# cryobondr-qbit2-pqc.net
KiCad netlist of a schematic drawn in EAGLE
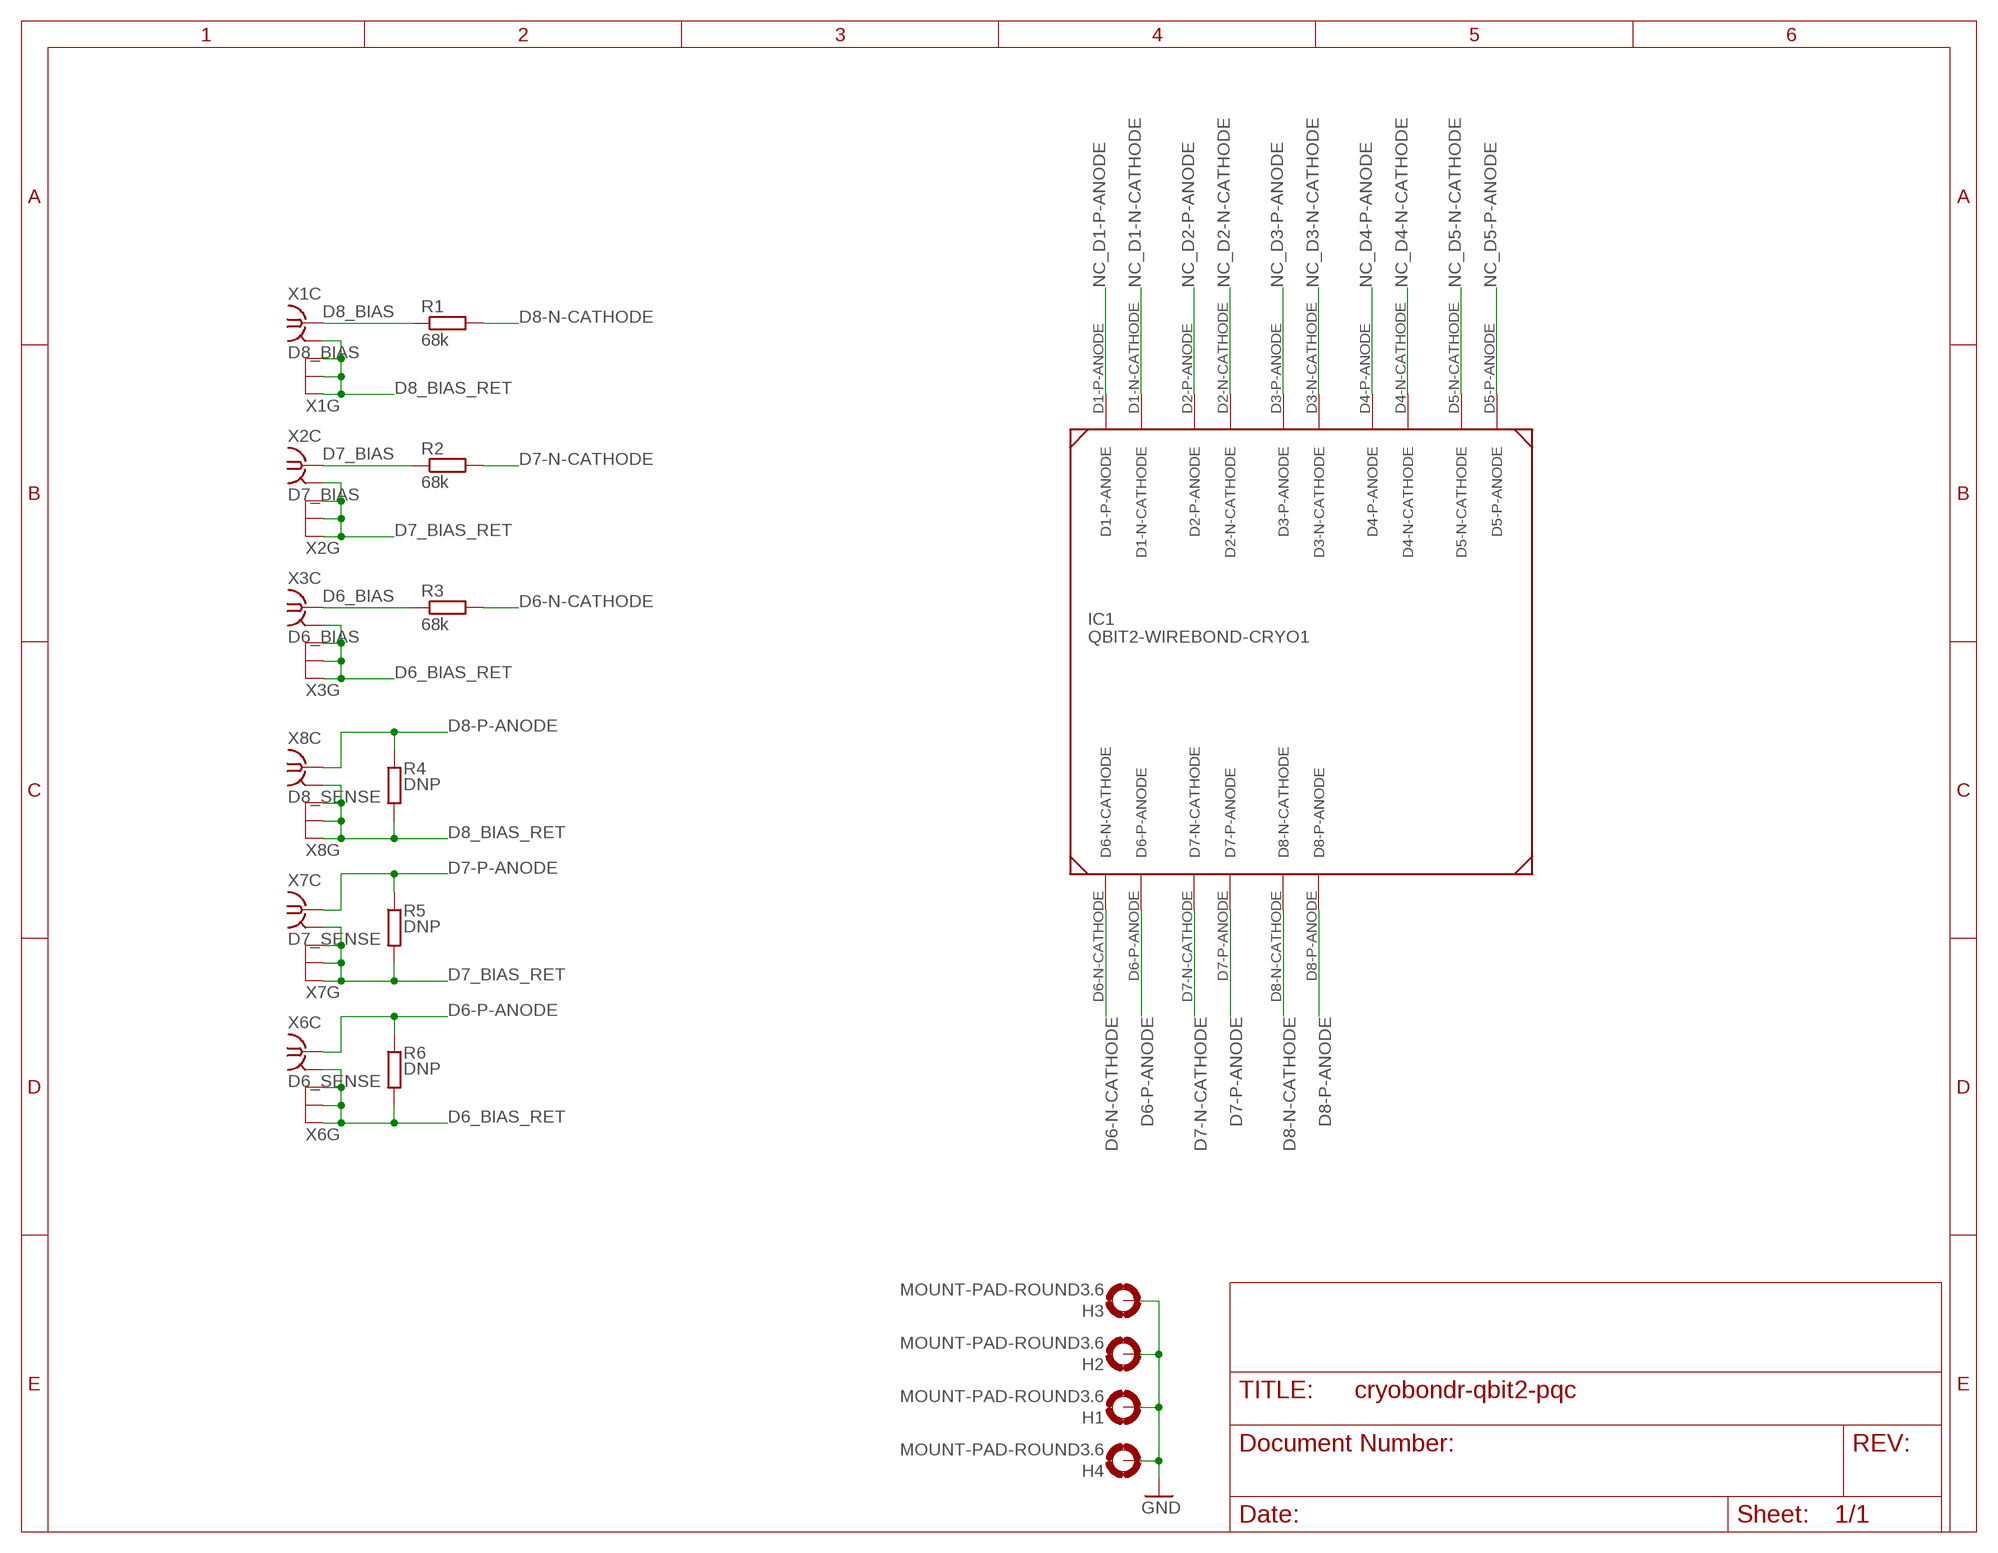
[diagram p0: schematic, sheet 1]

(export (version "E")
  (design (tool "Eeschema 10.0.6"))
  (components
    (comp (ref "H1")
      (value "MOUNT-PAD-ROUND3.6")
      (footprint "eagle-import:3,6-PAD")
      (libsource (lib "eagle-import") (part "MOUNT-PAD-ROUND3.6"))
    )
    (comp (ref "H2")
      (value "MOUNT-PAD-ROUND3.6")
      (footprint "eagle-import:3,6-PAD")
      (libsource (lib "eagle-import") (part "MOUNT-PAD-ROUND3.6"))
    )
    (comp (ref "H3")
      (value "MOUNT-PAD-ROUND3.6")
      (footprint "eagle-import:3,6-PAD")
      (libsource (lib "eagle-import") (part "MOUNT-PAD-ROUND3.6"))
    )
    (comp (ref "H4")
      (value "MOUNT-PAD-ROUND3.6")
      (footprint "eagle-import:3,6-PAD")
      (libsource (lib "eagle-import") (part "MOUNT-PAD-ROUND3.6"))
    )
    (comp (ref "IC1")
      (value "QBIT2-WIREBOND-CRYO1")
      (footprint "eagle-import:QBIT2-WIREBOND-CRYO1")
      (libsource (lib "eagle-import") (part "QBIT2-WIREBOND-CRYO1"))
    )
    (comp (ref "R1")
      (value "68k")
      (footprint "eagle-import:R0603")
      (libsource (lib "eagle-import") (part "R-EU_R0603"))
    )
    (comp (ref "R2")
      (value "68k")
      (footprint "eagle-import:R0603")
      (libsource (lib "eagle-import") (part "R-EU_R0603"))
    )
    (comp (ref "R3")
      (value "68k")
      (footprint "eagle-import:R0603")
      (libsource (lib "eagle-import") (part "R-EU_R0603"))
    )
    (comp (ref "R4")
      (value "DNP")
      (footprint "eagle-import:R0603")
      (libsource (lib "eagle-import") (part "R-EU_R0603"))
    )
    (comp (ref "R5")
      (value "DNP")
      (footprint "eagle-import:R0603")
      (libsource (lib "eagle-import") (part "R-EU_R0603"))
    )
    (comp (ref "R6")
      (value "DNP")
      (footprint "eagle-import:R0603")
      (libsource (lib "eagle-import") (part "R-EU_R0603"))
    )
    (comp (ref "X1")
      (value "D8_BIAS")
      (footprint "eagle-import:MMCX-SMT")
      (libsource (lib "eagle-import") (part "MMCX"))
    )
    (comp (ref "X2")
      (value "D7_BIAS")
      (footprint "eagle-import:MMCX-SMT")
      (libsource (lib "eagle-import") (part "MMCX"))
    )
    (comp (ref "X3")
      (value "D6_BIAS")
      (footprint "eagle-import:MMCX-SMT")
      (libsource (lib "eagle-import") (part "MMCX"))
    )
    (comp (ref "X6")
      (value "D6_SENSE")
      (footprint "eagle-import:MMCX-SMT")
      (libsource (lib "eagle-import") (part "MMCX"))
    )
    (comp (ref "X7")
      (value "D7_SENSE")
      (footprint "eagle-import:MMCX-SMT")
      (libsource (lib "eagle-import") (part "MMCX"))
    )
    (comp (ref "X8")
      (value "D8_SENSE")
      (footprint "eagle-import:MMCX-SMT")
      (libsource (lib "eagle-import") (part "MMCX"))
    )
  )
  (nets
    (net (code "1") (name "/D6-N-CATHODE") (class "Default")
      (node (ref "IC1") (pin "D6-N-CATHODE") (pinfunction "D6-N-CATHODE_D6-N-CATHODE") (pintype "bidirectional"))
      (node (ref "R3") (pin "2") (pinfunction "2_2") (pintype "passive"))
    )
    (net (code "2") (name "/D6-P-ANODE") (class "Default")
      (node (ref "IC1") (pin "D6-P-ANODE") (pinfunction "D6-P-ANODE_D6-P-ANODE") (pintype "bidirectional"))
      (node (ref "R6") (pin "1") (pinfunction "1_1") (pintype "passive"))
      (node (ref "X6") (pin "S") (pinfunction "1_S") (pintype "passive"))
    )
    (net (code "3") (name "/D6_BIAS") (class "Default")
      (node (ref "R3") (pin "1") (pinfunction "1_1") (pintype "passive"))
      (node (ref "X3") (pin "S") (pinfunction "1_S") (pintype "passive"))
    )
    (net (code "4") (name "/D6_BIAS_RET") (class "Default")
      (node (ref "R6") (pin "2") (pinfunction "2_2") (pintype "passive"))
      (node (ref "X3") (pin "G1") (pinfunction "GND_G1") (pintype "power_in"))
      (node (ref "X3") (pin "G2") (pinfunction "GND_G2") (pintype "power_in"))
      (node (ref "X3") (pin "G3") (pinfunction "GND_G3") (pintype "power_in"))
      (node (ref "X3") (pin "G4") (pinfunction "GND_G4") (pintype "power_in"))
      (node (ref "X6") (pin "G1") (pinfunction "GND_G1") (pintype "power_in"))
      (node (ref "X6") (pin "G2") (pinfunction "GND_G2") (pintype "power_in"))
      (node (ref "X6") (pin "G3") (pinfunction "GND_G3") (pintype "power_in"))
      (node (ref "X6") (pin "G4") (pinfunction "GND_G4") (pintype "power_in"))
    )
    (net (code "5") (name "/D7-N-CATHODE") (class "Default")
      (node (ref "IC1") (pin "D7-N-CATHODE") (pinfunction "D7-N-CATHODE_D7-N-CATHODE") (pintype "bidirectional"))
      (node (ref "R2") (pin "2") (pinfunction "2_2") (pintype "passive"))
    )
    (net (code "6") (name "/D7-P-ANODE") (class "Default")
      (node (ref "IC1") (pin "D7-P-ANODE") (pinfunction "D7-P-ANODE_D7-P-ANODE") (pintype "bidirectional"))
      (node (ref "R5") (pin "1") (pinfunction "1_1") (pintype "passive"))
      (node (ref "X7") (pin "S") (pinfunction "1_S") (pintype "passive"))
    )
    (net (code "7") (name "/D7_BIAS") (class "Default")
      (node (ref "R2") (pin "1") (pinfunction "1_1") (pintype "passive"))
      (node (ref "X2") (pin "S") (pinfunction "1_S") (pintype "passive"))
    )
    (net (code "8") (name "/D7_BIAS_RET") (class "Default")
      (node (ref "R5") (pin "2") (pinfunction "2_2") (pintype "passive"))
      (node (ref "X2") (pin "G1") (pinfunction "GND_G1") (pintype "power_in"))
      (node (ref "X2") (pin "G2") (pinfunction "GND_G2") (pintype "power_in"))
      (node (ref "X2") (pin "G3") (pinfunction "GND_G3") (pintype "power_in"))
      (node (ref "X2") (pin "G4") (pinfunction "GND_G4") (pintype "power_in"))
      (node (ref "X7") (pin "G1") (pinfunction "GND_G1") (pintype "power_in"))
      (node (ref "X7") (pin "G2") (pinfunction "GND_G2") (pintype "power_in"))
      (node (ref "X7") (pin "G3") (pinfunction "GND_G3") (pintype "power_in"))
      (node (ref "X7") (pin "G4") (pinfunction "GND_G4") (pintype "power_in"))
    )
    (net (code "9") (name "/D8-N-CATHODE") (class "Default")
      (node (ref "IC1") (pin "D8-N-CATHODE") (pinfunction "D8-N-CATHODE_D8-N-CATHODE") (pintype "bidirectional"))
      (node (ref "R1") (pin "2") (pinfunction "2_2") (pintype "passive"))
    )
    (net (code "10") (name "/D8-P-ANODE") (class "Default")
      (node (ref "IC1") (pin "D8-P-ANODE") (pinfunction "D8-P-ANODE_D8-P-ANODE") (pintype "bidirectional"))
      (node (ref "R4") (pin "1") (pinfunction "1_1") (pintype "passive"))
      (node (ref "X8") (pin "S") (pinfunction "1_S") (pintype "passive"))
    )
    (net (code "11") (name "/D8_BIAS") (class "Default")
      (node (ref "R1") (pin "1") (pinfunction "1_1") (pintype "passive"))
      (node (ref "X1") (pin "S") (pinfunction "1_S") (pintype "passive"))
    )
    (net (code "12") (name "/D8_BIAS_RET") (class "Default")
      (node (ref "R4") (pin "2") (pinfunction "2_2") (pintype "passive"))
      (node (ref "X1") (pin "G1") (pinfunction "GND_G1") (pintype "power_in"))
      (node (ref "X1") (pin "G2") (pinfunction "GND_G2") (pintype "power_in"))
      (node (ref "X1") (pin "G3") (pinfunction "GND_G3") (pintype "power_in"))
      (node (ref "X1") (pin "G4") (pinfunction "GND_G4") (pintype "power_in"))
      (node (ref "X8") (pin "G1") (pinfunction "GND_G1") (pintype "power_in"))
      (node (ref "X8") (pin "G2") (pinfunction "GND_G2") (pintype "power_in"))
      (node (ref "X8") (pin "G3") (pinfunction "GND_G3") (pintype "power_in"))
      (node (ref "X8") (pin "G4") (pinfunction "GND_G4") (pintype "power_in"))
    )
    (net (code "13") (name "/NC_D1-N-CATHODE") (class "Default")
      (node (ref "IC1") (pin "D1-N-CATHODE") (pinfunction "D1-N-CATHODE_D1-N-CATHODE") (pintype "bidirectional"))
    )
    (net (code "14") (name "/NC_D1-P-ANODE") (class "Default")
      (node (ref "IC1") (pin "D1-P-ANODE") (pinfunction "D1-P-ANODE_D1-P-ANODE") (pintype "bidirectional"))
    )
    (net (code "15") (name "/NC_D2-N-CATHODE") (class "Default")
      (node (ref "IC1") (pin "D2-N-CATHODE") (pinfunction "D2-N-CATHODE_D2-N-CATHODE") (pintype "bidirectional"))
    )
    (net (code "16") (name "/NC_D2-P-ANODE") (class "Default")
      (node (ref "IC1") (pin "D2-P-ANODE") (pinfunction "D2-P-ANODE_D2-P-ANODE") (pintype "bidirectional"))
    )
    (net (code "17") (name "/NC_D3-N-CATHODE") (class "Default")
      (node (ref "IC1") (pin "D3-N-CATHODE") (pinfunction "D3-N-CATHODE_D3-N-CATHODE") (pintype "bidirectional"))
    )
    (net (code "18") (name "/NC_D3-P-ANODE") (class "Default")
      (node (ref "IC1") (pin "D3-P-ANODE") (pinfunction "D3-P-ANODE_D3-P-ANODE") (pintype "bidirectional"))
    )
    (net (code "19") (name "/NC_D4-N-CATHODE") (class "Default")
      (node (ref "IC1") (pin "D4-N-CATHODE") (pinfunction "D4-N-CATHODE_D4-N-CATHODE") (pintype "bidirectional"))
    )
    (net (code "20") (name "/NC_D4-P-ANODE") (class "Default")
      (node (ref "IC1") (pin "D4-P-ANODE") (pinfunction "D4-P-ANODE_D4-P-ANODE") (pintype "bidirectional"))
    )
    (net (code "21") (name "/NC_D5-N-CATHODE") (class "Default")
      (node (ref "IC1") (pin "D5-N-CATHODE") (pinfunction "D5-N-CATHODE_D5-N-CATHODE") (pintype "bidirectional"))
    )
    (net (code "22") (name "/NC_D5-P-ANODE") (class "Default")
      (node (ref "IC1") (pin "D5-P-ANODE") (pinfunction "D5-P-ANODE_D5-P-ANODE") (pintype "bidirectional"))
    )
    (net (code "23") (name "GND") (class "Default")
      (node (ref "H1") (pin "B3,6") (pinfunction "MOUNT_B3,6") (pintype "passive"))
      (node (ref "H2") (pin "B3,6") (pinfunction "MOUNT_B3,6") (pintype "passive"))
      (node (ref "H3") (pin "B3,6") (pinfunction "MOUNT_B3,6") (pintype "passive"))
      (node (ref "H4") (pin "B3,6") (pinfunction "MOUNT_B3,6") (pintype "passive"))
    )
  )
)
